# wifi_reprap2.net
KiCad netlist of a schematic drawn in EAGLE
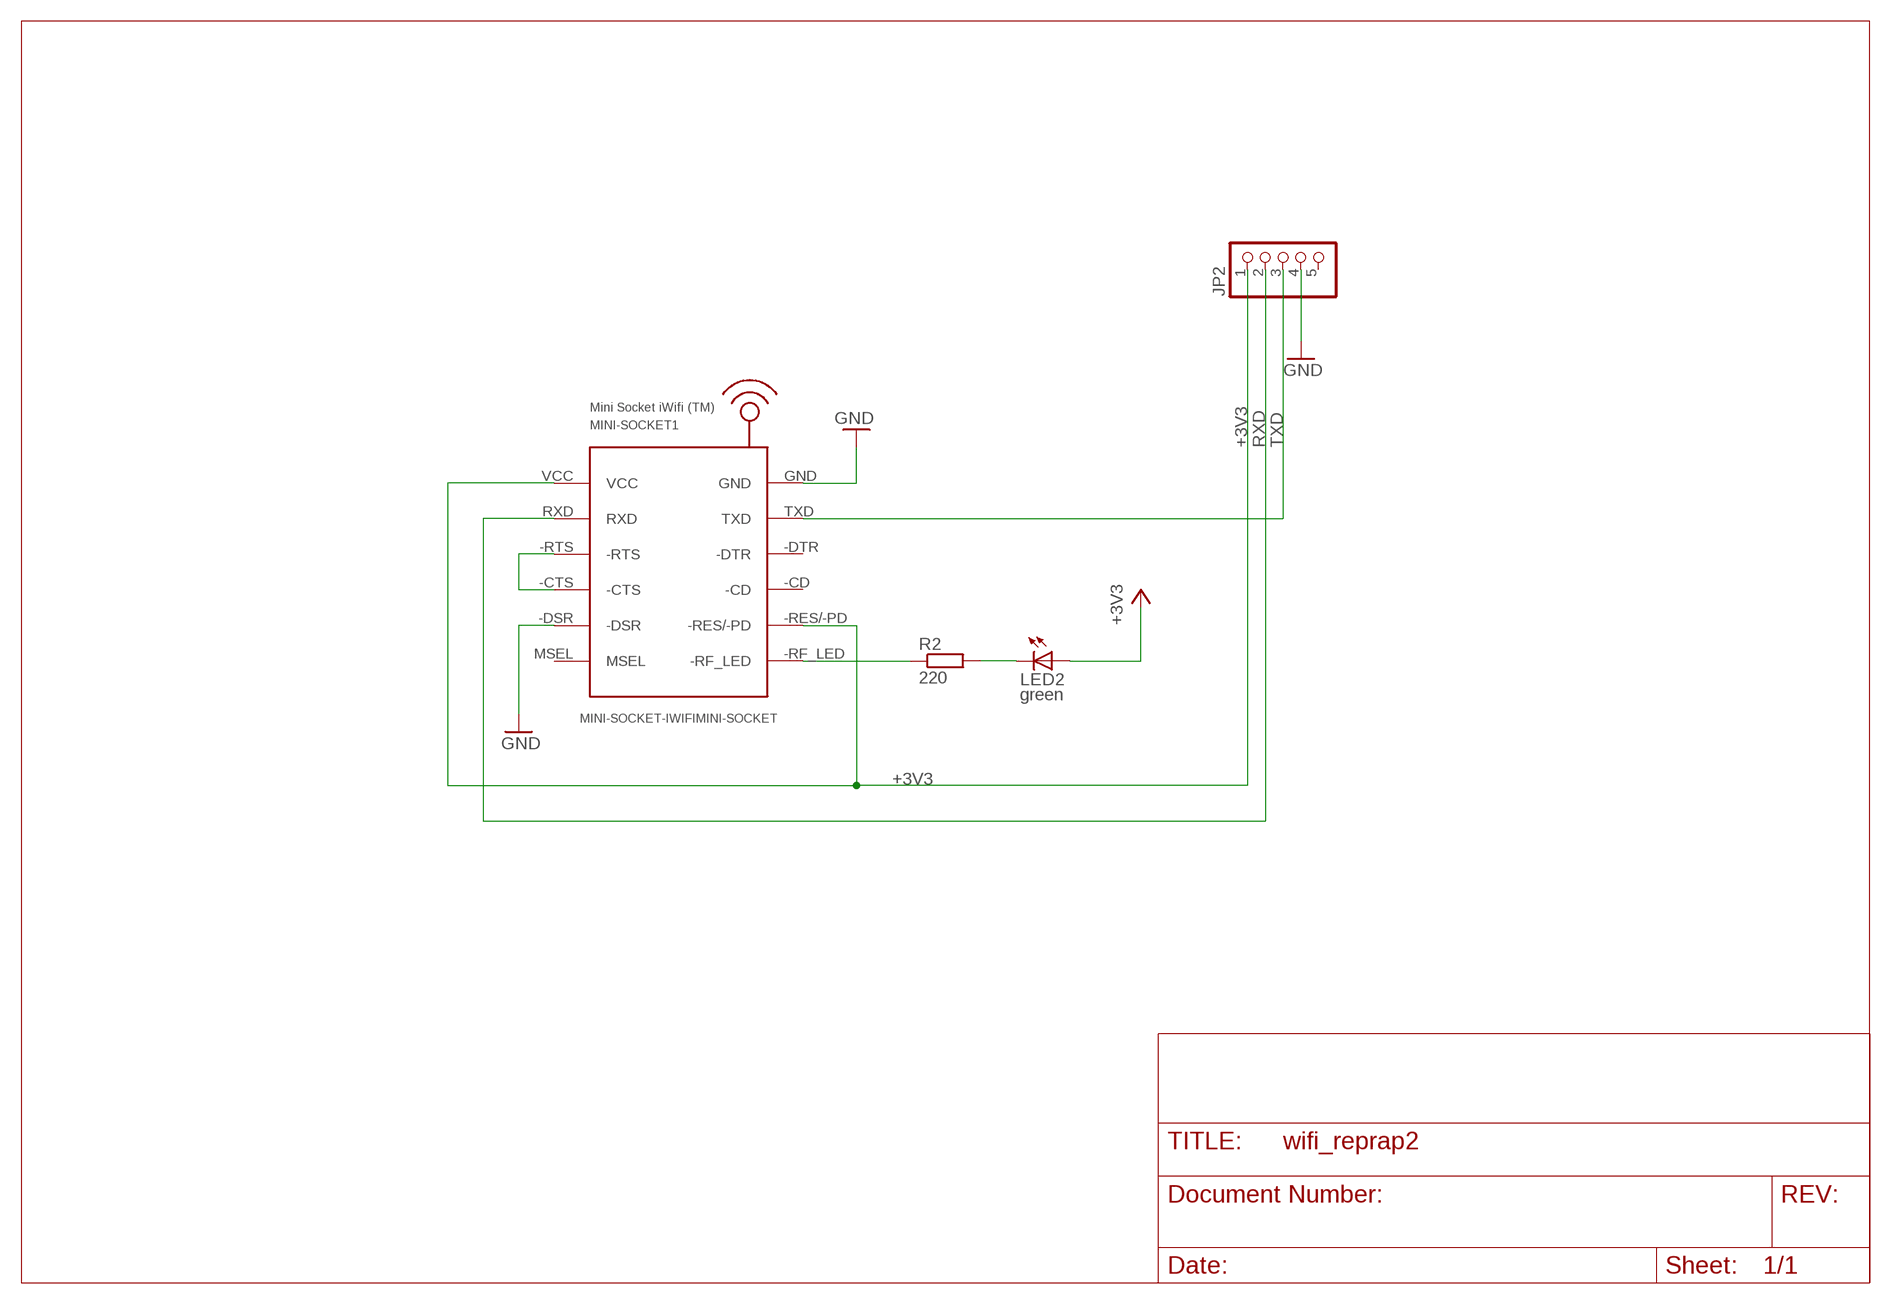
[diagram p0: schematic, sheet 1]

(export (version "E")
  (design (tool "Eeschema 10.0.6"))
  (components
    (comp (ref "JP2")
      (value "PINHD-1X5")
      (footprint "eagle-import:1X05")
      (libsource (lib "eagle-import") (part "PINHD-1X5"))
    )
    (comp (ref "LED2")
      (value "green")
      (footprint "eagle-import:LED5MM")
      (libsource (lib "eagle-import") (part "LED5MM"))
    )
    (comp (ref "MINI-SOCKET1")
      (value "MINI-SOCKET-IWIFIMINI-SOCKET")
      (footprint "eagle-import:MINI-SOCKET-IWIFI")
      (libsource (lib "eagle-import") (part "MINI-SOCKET-IWIFIMINI-SOCKET"))
    )
    (comp (ref "R2")
      (value "220")
      (footprint "eagle-import:0207_10")
      (libsource (lib "eagle-import") (part "R-EU_0207/10"))
    )
  )
  (nets
    (net (code "1") (name "+3V3") (class "Default")
      (node (ref "JP2") (pin "1") (pinfunction "1_1") (pintype "passive"))
      (node (ref "LED2") (pin "A") (pinfunction "A_A") (pintype "passive"))
      (node (ref "MINI-SOCKET1") (pin "-RES/-PD") (pinfunction "-RES/-PD_-RES/-PD") (pintype "input"))
      (node (ref "MINI-SOCKET1") (pin "VCC") (pinfunction "VCC_VCC") (pintype "power_in"))
    )
    (net (code "2") (name "/RXD") (class "Default")
      (node (ref "JP2") (pin "2") (pinfunction "2_2") (pintype "passive"))
      (node (ref "MINI-SOCKET1") (pin "RXD") (pinfunction "RXD_RXD") (pintype "input"))
    )
    (net (code "3") (name "/TXD") (class "Default")
      (node (ref "JP2") (pin "3") (pinfunction "3_3") (pintype "passive"))
      (node (ref "MINI-SOCKET1") (pin "TXD") (pinfunction "TXD_TXD") (pintype "output"))
    )
    (net (code "4") (name "GND") (class "Default")
      (node (ref "JP2") (pin "4") (pinfunction "4_4") (pintype "passive"))
      (node (ref "MINI-SOCKET1") (pin "-DSR") (pinfunction "-DSR_-DSR") (pintype "input"))
      (node (ref "MINI-SOCKET1") (pin "GND") (pinfunction "GND_GND") (pintype "power_in"))
    )
    (net (code "5") (name "Net-(LED2-C)") (class "Default")
      (node (ref "LED2") (pin "K") (pinfunction "C_K") (pintype "passive"))
      (node (ref "R2") (pin "2") (pinfunction "2_2") (pintype "passive"))
    )
    (net (code "6") (name "Net-(MINI-SOCKET1-Pad-CTS)") (class "Default")
      (node (ref "MINI-SOCKET1") (pin "-CTS") (pinfunction "-CTS_-CTS") (pintype "input"))
      (node (ref "MINI-SOCKET1") (pin "-RTS") (pinfunction "-RTS_-RTS") (pintype "output"))
    )
    (net (code "7") (name "Net-(MINI-SOCKET1-Pad-RF_LED)") (class "Default")
      (node (ref "MINI-SOCKET1") (pin "-RF_LED") (pinfunction "-RF_LED_-RF_LED") (pintype "output"))
      (node (ref "R2") (pin "1") (pinfunction "1_1") (pintype "passive"))
    )
    (net (code "8") (name "unconnected-(JP2-Pad5)") (class "Default")
      (node (ref "JP2") (pin "5") (pinfunction "5_5") (pintype "passive"))
    )
    (net (code "9") (name "unconnected-(MINI-SOCKET1-Pad-CD)") (class "Default")
      (node (ref "MINI-SOCKET1") (pin "-CD") (pinfunction "-CD_-CD") (pintype "output"))
    )
    (net (code "10") (name "unconnected-(MINI-SOCKET1-Pad-DTR)") (class "Default")
      (node (ref "MINI-SOCKET1") (pin "-DTR") (pinfunction "-DTR_-DTR") (pintype "output"))
    )
    (net (code "11") (name "unconnected-(MINI-SOCKET1-PadMSEL)") (class "Default")
      (node (ref "MINI-SOCKET1") (pin "MSEL") (pinfunction "MSEL_MSEL") (pintype "input"))
    )
  )
)
